# main.net
KiCad netlist of a schematic drawn in Altium Designer
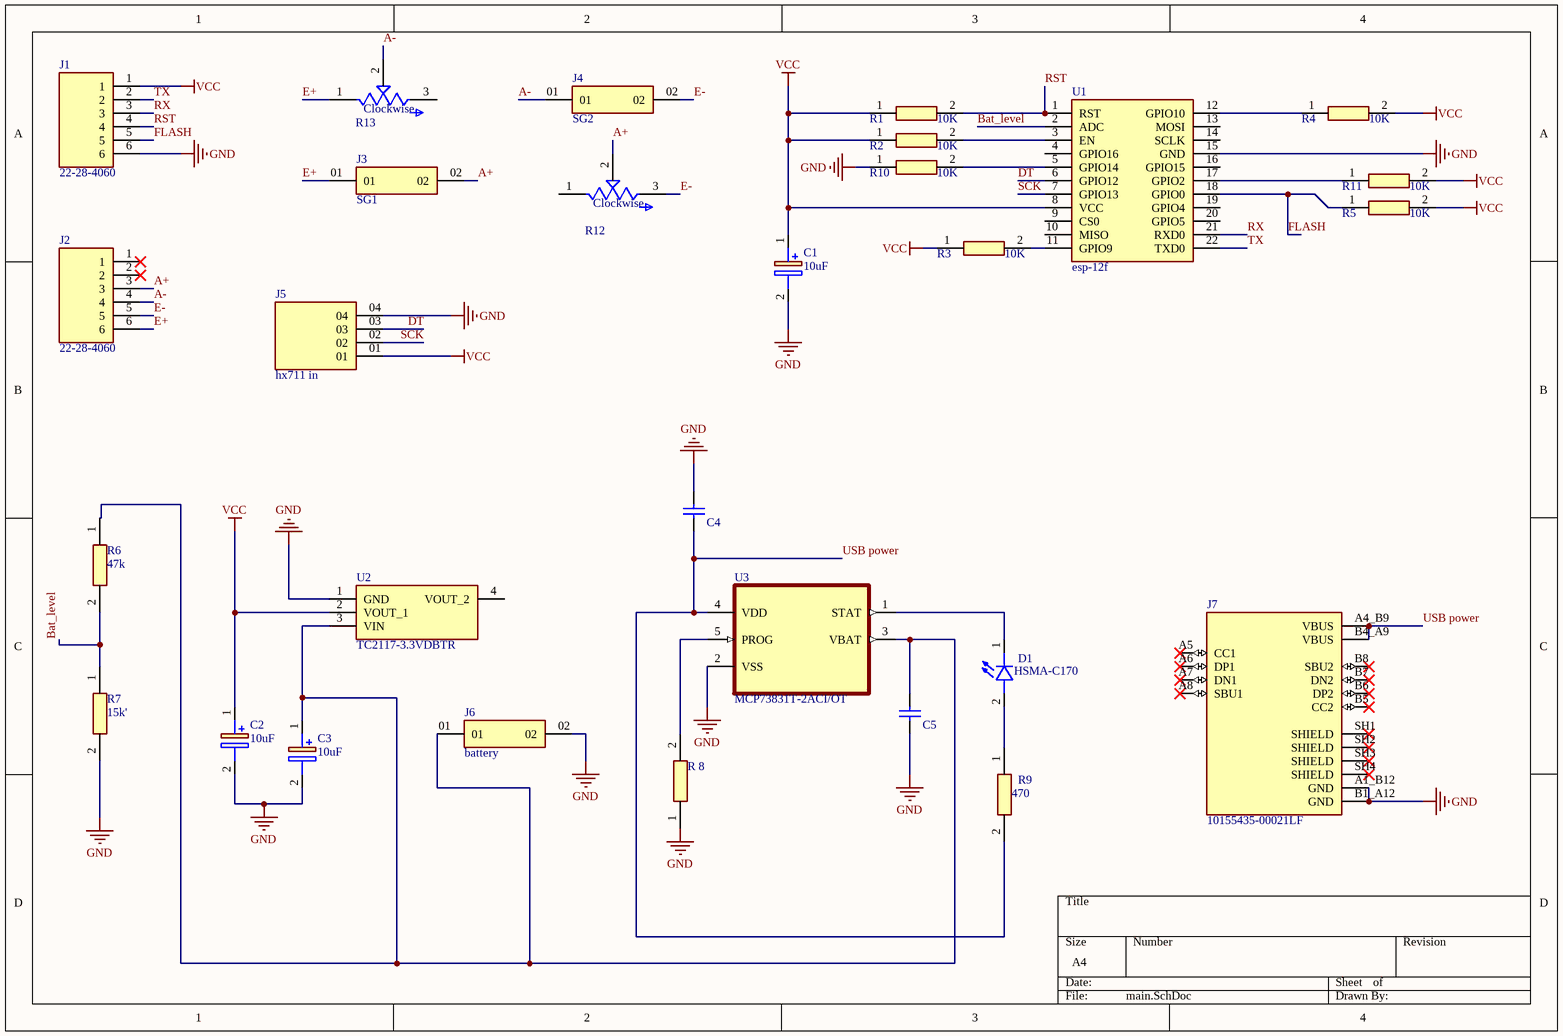
[diagram p0: main.SchDoc]

(export (version "E")
  (design (tool "Eeschema 10.0.6"))
  (components
    (comp (ref "C1")
      (value "10uF")
      (footprint "SamacSys:EEE1AA220WR")
      (description "Capacitor Polarised")
      (fields
        (field (name "MANUFACTURER_PART_NUMBER") "EEE-FN1C100R")
        (field (name "MOUSER PART NUMBER") "667-EEE-FN1C100R")
      )
      (libsource (lib "*") (part "EEE-FN1C100R"))
    )
    (comp (ref "C2")
      (value "10uF")
      (footprint "SamacSys:EEE1AA220WR")
      (description "Capacitor Polarised")
      (fields
        (field (name "MANUFACTURER_PART_NUMBER") "EEE-FN1C100R")
        (field (name "MOUSER PART NUMBER") "667-EEE-FN1C100R")
      )
      (libsource (lib "*") (part "EEE-FN1C100R"))
    )
    (comp (ref "C3")
      (value "10uF")
      (footprint "SamacSys:EEE1AA220WR")
      (description "Capacitor Polarised")
      (fields
        (field (name "MANUFACTURER_PART_NUMBER") "EEE-FN1C100R")
        (field (name "MOUSER PART NUMBER") "667-EEE-FN1C100R")
      )
      (libsource (lib "*") (part "EEE-FN1C100R"))
    )
    (comp (ref "C4")
      (value "4.7uF")
      (footprint "WCAP-CSGP_0805_L2W1.25H0.6_Reflow")
      (description "WCAP-CSGP Multilayer Ceramic Chip Capacitor, General Purpose, size 0805, NP0, 4.7pF, 50VDC")
      (fields
        (field (name "MANUFACTURER PART NUMBER") "885012007049")
        (field (name "MANUFACTURER") "Wurth Elektronik")
      )
      (libsource (lib "WCAP-CSGP") (part "885012007049"))
    )
    (comp (ref "C5")
      (value "4.7uF")
      (footprint "WCAP-CSGP_0805_L2W1.25H0.6_Reflow")
      (description "WCAP-CSGP Multilayer Ceramic Chip Capacitor, General Purpose, size 0805, NP0, 4.7pF, 50VDC")
      (fields
        (field (name "MANUFACTURER PART NUMBER") "885012007049")
        (field (name "MANUFACTURER") "Wurth Elektronik")
      )
      (libsource (lib "WCAP-CSGP") (part "885012007049"))
    )
    (comp (ref "D1")
      (value "HSMA-C170")
      (footprint "LED_HSMA-C170")
      (libsource (lib "HSMA-C170") (part "HSMA-C170"))
    )
    (comp (ref "J1")
      (value "22-28-4060")
      (footprint "HDRV6W66P0X254_1X6_1524X249X838P")
      (description "Connector")
      (fields (field (name "MOUSER PART NUMBER") "538-22-28-4060"))
      (libsource (lib "University of Moratuwa, Sri Lanka") (part "22-28-4060"))
    )
    (comp (ref "J2")
      (value "22-28-4060")
      (footprint "HDRV6W66P0X254_1X6_1524X249X838P")
      (description "Connector")
      (fields (field (name "MOUSER PART NUMBER") "538-22-28-4060"))
      (libsource (lib "University of Moratuwa, Sri Lanka") (part "22-28-4060"))
    )
    (comp (ref "J3")
      (value "SG1")
      (footprint "SAMTEC_MTSW-101-08-G-D-250")
      (fields (field (name "MP") "MTSW-101-08-G-D-250"))
      (libsource (lib "MTSW-101-08-G-D-250") (part "MTSW-101-08-G-D-250"))
    )
    (comp (ref "J4")
      (value "SG2")
      (footprint "SAMTEC_MTSW-101-08-G-D-250")
      (fields (field (name "MP") "MTSW-101-08-G-D-250"))
      (libsource (lib "MTSW-101-08-G-D-250") (part "MTSW-101-08-G-D-250"))
    )
    (comp (ref "J5")
      (value "hx711 in")
      (footprint "SAMTEC_TSW-104-16-G-S")
      (fields (field (name "MP") "TSW-104-16-G-S"))
      (libsource (lib "TSW-104-16-G-S") (part "TSW-104-16-G-S"))
    )
    (comp (ref "J6")
      (value "battery")
      (footprint "SAMTEC_MTSW-101-08-G-D-250")
      (fields (field (name "MP") "MTSW-101-08-G-D-250"))
      (libsource (lib "MTSW-101-08-G-D-250") (part "MTSW-101-08-G-D-250"))
    )
    (comp (ref "J7")
      (value "10155435-00021LF")
      (footprint "AMPHENOL_10155435-00021LF")
      (libsource (lib "10155435-00021LF") (part "10155435-00021LF"))
    )
    (comp (ref "R 8")
      (value "CR0805-JW-202ELF")
      (footprint "SamacSys:RESC2012X60N")
      (description "Resistor")
      (fields (field (name "MOUSER PART NUMBER") "652-CR0805JW-202ELF"))
      (libsource (lib "*") (part "CR0805-JW-202ELF"))
    )
    (comp (ref "R1")
      (value "10K")
      (footprint "SamacSys:RESC2012X60N")
      (description "Resistor")
      (fields
        (field (name "MANUFACTURER_PART_NUMBER") "CHP0805-FX-1002ELF")
        (field (name "MOUSER PART NUMBER") "652-CHP0805FX1002ELF")
      )
      (libsource (lib "") (part "CHP0805-FX-1002ELF_1"))
    )
    (comp (ref "R2")
      (value "10K")
      (footprint "SamacSys:RESC2012X60N")
      (description "Resistor")
      (fields
        (field (name "MANUFACTURER_PART_NUMBER") "CHP0805-FX-1002ELF")
        (field (name "MOUSER PART NUMBER") "652-CHP0805FX1002ELF")
      )
      (libsource (lib "") (part "CHP0805-FX-1002ELF_1"))
    )
    (comp (ref "R3")
      (value "10K")
      (footprint "SamacSys:RESC2012X60N")
      (description "Resistor")
      (fields
        (field (name "MANUFACTURER_PART_NUMBER") "CHP0805-FX-1002ELF")
        (field (name "MOUSER PART NUMBER") "652-CHP0805FX1002ELF")
      )
      (libsource (lib "") (part "CHP0805-FX-1002ELF_1"))
    )
    (comp (ref "R4")
      (value "10K")
      (footprint "SamacSys:RESC2012X60N")
      (description "Resistor")
      (fields
        (field (name "MANUFACTURER_PART_NUMBER") "CHP0805-FX-1002ELF")
        (field (name "MOUSER PART NUMBER") "652-CHP0805FX1002ELF")
      )
      (libsource (lib "") (part "CHP0805-FX-1002ELF_1"))
    )
    (comp (ref "R5")
      (value "10K")
      (footprint "SamacSys:RESC2012X60N")
      (description "Resistor")
      (fields
        (field (name "MANUFACTURER_PART_NUMBER") "CHP0805-FX-1002ELF")
        (field (name "MOUSER PART NUMBER") "652-CHP0805FX1002ELF")
      )
      (libsource (lib "") (part "CHP0805-FX-1002ELF_1"))
    )
    (comp (ref "R6")
      (value "47k")
      (footprint "SamacSys:RESC2012X60N")
      (description "Resistor")
      (fields
        (field (name "MANUFACTURER_PART_NUMBER") "CHP0805-FX-1002ELF")
        (field (name "MOUSER PART NUMBER") "652-CHP0805FX1002ELF")
      )
      (libsource (lib "*") (part "CHP0805-FX-1002ELF"))
    )
    (comp (ref "R7")
      (value "15k'")
      (footprint "SamacSys:RESC2012X60N")
      (description "Resistor")
      (fields
        (field (name "MANUFACTURER_PART_NUMBER") "CHP0805-FX-1002ELF")
        (field (name "MOUSER PART NUMBER") "652-CHP0805FX1002ELF")
      )
      (libsource (lib "*") (part "CHP0805-FX-1002ELF"))
    )
    (comp (ref "R9")
      (value "470")
      (footprint "SamacSys:RESC2012X60N")
      (description "Resistor")
      (fields
        (field (name "MANUFACTURER_PART_NUMBER") "CHP0805-FX-1002ELF")
        (field (name "MOUSER PART NUMBER") "652-CHP0805FX1002ELF")
      )
      (libsource (lib "*") (part "CHP0805-FX-1002ELF"))
    )
    (comp (ref "R10")
      (value "10K")
      (footprint "SamacSys:RESC2012X60N")
      (description "Resistor")
      (fields
        (field (name "MANUFACTURER_PART_NUMBER") "CHP0805-FX-1002ELF")
        (field (name "MOUSER PART NUMBER") "652-CHP0805FX1002ELF")
      )
      (libsource (lib "") (part "CHP0805-FX-1002ELF_1"))
    )
    (comp (ref "R11")
      (value "10K")
      (footprint "SamacSys:RESC2012X60N")
      (description "Resistor")
      (fields
        (field (name "MANUFACTURER_PART_NUMBER") "CHP0805-FX-1002ELF")
        (field (name "MOUSER PART NUMBER") "652-CHP0805FX1002ELF")
      )
      (libsource (lib "") (part "CHP0805-FX-1002ELF_1"))
    )
    (comp (ref "R12")
      (value "PV37W501C01B00")
      (footprint "TRIM_PV37W501C01B00")
      (description "500 Ohms 0.25W, 1/4W PC Pins Through Hole Trimmer Potentiometer Cermet 12.0 Turn Top Adjustment")
      (fields (field (name "MF") "Bourns"))
      (libsource (lib "PV37W501C01B00") (part "PV37W501C01B00"))
    )
    (comp (ref "R13")
      (value "PV37W501C01B00")
      (footprint "TRIM_PV37W501C01B00")
      (description "500 Ohms 0.25W, 1/4W PC Pins Through Hole Trimmer Potentiometer Cermet 12.0 Turn Top Adjustment")
      (fields (field (name "MF") "Bourns"))
      (libsource (lib "PV37W501C01B00") (part "PV37W501C01B00"))
    )
    (comp (ref "U1")
      (value "esp-12f")
      (footprint "SamacSys:esp12f")
      (description "Integrated Circuit")
      (libsource (lib "*") (part "esp-12f"))
    )
    (comp (ref "U2")
      (value "TC2117-3.3VDBTR")
      (footprint "SOT230P700X180-4N")
      (description "Power Supply")
      (fields (field (name "MOUSER PART NUMBER") "579-TC2117-3.3VDBTR"))
      (libsource (lib "*") (part "TC2117-3.3VDBTR"))
    )
    (comp (ref "U3")
      (value "MCP73831T-2ACI/OT")
      (footprint "SOT95P280X145-5N")
      (description "Charger IC Lithium Ion/Polymer SOT-23-5")
      (fields (field (name "MF") "Microchip"))
      (libsource (lib "MCP73831T-2ACI_OT") (part "MCP73831T-2ACI/OT"))
    )
  )
  (nets
    (net (code "1") (name "/A+") (class "Default")
      (node (ref "J2") (pin "3") (pinfunction "3_3") (pintype "passive"))
      (node (ref "J3") (pin "02") (pinfunction "02_02") (pintype "passive"))
      (node (ref "R12") (pin "2") (pinfunction "2_2") (pintype "passive"))
    )
    (net (code "2") (name "/A-") (class "Default")
      (node (ref "J2") (pin "4") (pinfunction "4_4") (pintype "passive"))
      (node (ref "J4") (pin "01") (pinfunction "01_01") (pintype "passive"))
      (node (ref "R13") (pin "2") (pinfunction "2_2") (pintype "passive"))
    )
    (net (code "3") (name "/Bat_level") (class "Default")
      (node (ref "R6") (pin "2") (pinfunction "2_2") (pintype "passive"))
      (node (ref "R7") (pin "1") (pinfunction "1_1") (pintype "passive"))
      (node (ref "U1") (pin "2") (pinfunction "ADC_2") (pintype "passive"))
    )
    (net (code "4") (name "/DT") (class "Default")
      (node (ref "J5") (pin "03") (pinfunction "03_03") (pintype "passive"))
      (node (ref "U1") (pin "6") (pinfunction "GPIO12_6") (pintype "passive"))
    )
    (net (code "5") (name "/E+") (class "Default")
      (node (ref "J2") (pin "6") (pinfunction "6_6") (pintype "passive"))
      (node (ref "J3") (pin "01") (pinfunction "01_01") (pintype "passive"))
      (node (ref "R13") (pin "1") (pinfunction "1_1") (pintype "passive"))
    )
    (net (code "6") (name "/E-") (class "Default")
      (node (ref "J2") (pin "5") (pinfunction "5_5") (pintype "passive"))
      (node (ref "J4") (pin "02") (pinfunction "02_02") (pintype "passive"))
      (node (ref "R12") (pin "3") (pinfunction "3_3") (pintype "passive"))
    )
    (net (code "7") (name "/FLASH") (class "Default")
      (node (ref "J1") (pin "5") (pinfunction "5_5") (pintype "passive"))
      (node (ref "R5") (pin "1") (pinfunction "1_1") (pintype "passive"))
      (node (ref "U1") (pin "18") (pinfunction "GPIO0_18") (pintype "passive"))
    )
    (net (code "8") (name "/RST") (class "Default")
      (node (ref "J1") (pin "4") (pinfunction "4_4") (pintype "passive"))
      (node (ref "R1") (pin "2") (pinfunction "2_2") (pintype "passive"))
      (node (ref "U1") (pin "1") (pinfunction "RST_1") (pintype "passive"))
    )
    (net (code "9") (name "/RX") (class "Default")
      (node (ref "J1") (pin "3") (pinfunction "3_3") (pintype "passive"))
      (node (ref "U1") (pin "21") (pinfunction "RXD0_21") (pintype "passive"))
    )
    (net (code "10") (name "/SCK") (class "Default")
      (node (ref "J5") (pin "02") (pinfunction "02_02") (pintype "passive"))
      (node (ref "U1") (pin "7") (pinfunction "GPIO13_7") (pintype "passive"))
    )
    (net (code "11") (name "/TX") (class "Default")
      (node (ref "J1") (pin "2") (pinfunction "2_2") (pintype "passive"))
      (node (ref "U1") (pin "22") (pinfunction "TXD0_22") (pintype "passive"))
    )
    (net (code "12") (name "/USB power") (class "Default")
      (node (ref "C4") (pin "2") (pinfunction "2_2") (pintype "passive"))
      (node (ref "J7") (pin "A4_B9") (pinfunction "VBUS_A4_B9") (pintype "power_in"))
      (node (ref "J7") (pin "B4_A9") (pinfunction "VBUS_B4_A9") (pintype "power_in"))
      (node (ref "R9") (pin "2") (pinfunction "2_2") (pintype "passive"))
      (node (ref "U3") (pin "4") (pinfunction "VDD_4") (pintype "power_in"))
    )
    (net (code "13") (name "GND") (class "Default")
      (node (ref "C1") (pin "2") (pinfunction "-_2") (pintype "passive"))
      (node (ref "C2") (pin "2") (pinfunction "-_2") (pintype "passive"))
      (node (ref "C3") (pin "2") (pinfunction "-_2") (pintype "passive"))
      (node (ref "C4") (pin "1") (pinfunction "1_1") (pintype "passive"))
      (node (ref "C5") (pin "1") (pinfunction "1_1") (pintype "passive"))
      (node (ref "J1") (pin "6") (pinfunction "6_6") (pintype "passive"))
      (node (ref "J5") (pin "04") (pinfunction "04_04") (pintype "passive"))
      (node (ref "J6") (pin "02") (pinfunction "02_02") (pintype "passive"))
      (node (ref "J7") (pin "A1_B12") (pinfunction "GND_A1_B12") (pintype "power_in"))
      (node (ref "J7") (pin "B1_A12") (pinfunction "GND_B1_A12") (pintype "power_in"))
      (node (ref "R 8") (pin "1") (pinfunction "1_1") (pintype "passive"))
      (node (ref "R10") (pin "1") (pinfunction "1_1") (pintype "passive"))
      (node (ref "R7") (pin "2") (pinfunction "2_2") (pintype "passive"))
      (node (ref "U1") (pin "15") (pinfunction "GND_15") (pintype "passive"))
      (node (ref "U2") (pin "1") (pinfunction "GND_1") (pintype "passive"))
      (node (ref "U3") (pin "2") (pinfunction "VSS_2") (pintype "power_in"))
    )
    (net (code "14") (name "Net-(C3-+)") (class "Default")
      (node (ref "C3") (pin "1") (pinfunction "+_1") (pintype "passive"))
      (node (ref "C5") (pin "2") (pinfunction "2_2") (pintype "passive"))
      (node (ref "J6") (pin "01") (pinfunction "01_01") (pintype "passive"))
      (node (ref "R6") (pin "1") (pinfunction "1_1") (pintype "passive"))
      (node (ref "U2") (pin "3") (pinfunction "VIN_3") (pintype "passive"))
      (node (ref "U3") (pin "3") (pinfunction "VBAT_3") (pintype "output"))
    )
    (net (code "15") (name "Net-(D1-A)") (class "Default")
      (node (ref "D1") (pin "2") (pinfunction "A_2") (pintype "passive"))
      (node (ref "R9") (pin "1") (pinfunction "1_1") (pintype "passive"))
    )
    (net (code "16") (name "Net-(D1-C)") (class "Default")
      (node (ref "D1") (pin "1") (pinfunction "C_1") (pintype "passive"))
      (node (ref "U3") (pin "1") (pinfunction "STAT_1") (pintype "output"))
    )
    (net (code "17") (name "Net-(U1-EN)") (class "Default")
      (node (ref "R2") (pin "2") (pinfunction "2_2") (pintype "passive"))
      (node (ref "U1") (pin "3") (pinfunction "EN_3") (pintype "passive"))
    )
    (net (code "18") (name "Net-(U1-GPIO2)") (class "Default")
      (node (ref "R11") (pin "1") (pinfunction "1_1") (pintype "passive"))
      (node (ref "U1") (pin "17") (pinfunction "GPIO2_17") (pintype "passive"))
    )
    (net (code "19") (name "Net-(U1-GPIO9)") (class "Default")
      (node (ref "R3") (pin "2") (pinfunction "2_2") (pintype "passive"))
      (node (ref "U1") (pin "11") (pinfunction "GPIO9_11") (pintype "passive"))
    )
    (net (code "20") (name "Net-(U1-GPIO10)") (class "Default")
      (node (ref "R4") (pin "1") (pinfunction "1_1") (pintype "passive"))
      (node (ref "U1") (pin "12") (pinfunction "GPIO10_12") (pintype "passive"))
    )
    (net (code "21") (name "Net-(U1-GPIO14)") (class "Default")
      (node (ref "R10") (pin "2") (pinfunction "2_2") (pintype "passive"))
      (node (ref "U1") (pin "5") (pinfunction "GPIO14_5") (pintype "passive"))
    )
    (net (code "22") (name "Net-(U3-PROG)") (class "Default")
      (node (ref "R 8") (pin "2") (pinfunction "2_2") (pintype "passive"))
      (node (ref "U3") (pin "5") (pinfunction "PROG_5") (pintype "input"))
    )
    (net (code "23") (name "VCC") (class "Default")
      (node (ref "C1") (pin "1") (pinfunction "+_1") (pintype "passive"))
      (node (ref "C2") (pin "1") (pinfunction "+_1") (pintype "passive"))
      (node (ref "J1") (pin "1") (pinfunction "1_1") (pintype "passive"))
      (node (ref "J5") (pin "01") (pinfunction "01_01") (pintype "passive"))
      (node (ref "R1") (pin "1") (pinfunction "1_1") (pintype "passive"))
      (node (ref "R11") (pin "2") (pinfunction "2_2") (pintype "passive"))
      (node (ref "R2") (pin "1") (pinfunction "1_1") (pintype "passive"))
      (node (ref "R3") (pin "1") (pinfunction "1_1") (pintype "passive"))
      (node (ref "R4") (pin "2") (pinfunction "2_2") (pintype "passive"))
      (node (ref "R5") (pin "2") (pinfunction "2_2") (pintype "passive"))
      (node (ref "U1") (pin "8") (pinfunction "VCC_8") (pintype "passive"))
      (node (ref "U2") (pin "2") (pinfunction "VOUT_1_2") (pintype "passive"))
    )
    (net (code "24") (name "unconnected-(J2-Pad1)") (class "Default")
      (node (ref "J2") (pin "1") (pinfunction "1_1") (pintype "passive+no_connect"))
    )
    (net (code "25") (name "unconnected-(J2-Pad2)") (class "Default")
      (node (ref "J2") (pin "2") (pinfunction "2_2") (pintype "passive+no_connect"))
    )
    (net (code "26") (name "unconnected-(J7-CC1-PadA5)") (class "Default")
      (node (ref "J7") (pin "A5") (pinfunction "CC1_A5") (pintype "bidirectional+no_connect"))
    )
    (net (code "27") (name "unconnected-(J7-CC2-PadB5)") (class "Default")
      (node (ref "J7") (pin "B5") (pinfunction "CC2_B5") (pintype "bidirectional+no_connect"))
    )
    (net (code "28") (name "unconnected-(J7-DN1-PadA7)") (class "Default")
      (node (ref "J7") (pin "A7") (pinfunction "DN1_A7") (pintype "bidirectional+no_connect"))
    )
    (net (code "29") (name "unconnected-(J7-DN2-PadB7)") (class "Default")
      (node (ref "J7") (pin "B7") (pinfunction "DN2_B7") (pintype "bidirectional+no_connect"))
    )
    (net (code "30") (name "unconnected-(J7-DP1-PadA6)") (class "Default")
      (node (ref "J7") (pin "A6") (pinfunction "DP1_A6") (pintype "bidirectional+no_connect"))
    )
    (net (code "31") (name "unconnected-(J7-DP2-PadB6)") (class "Default")
      (node (ref "J7") (pin "B6") (pinfunction "DP2_B6") (pintype "bidirectional+no_connect"))
    )
    (net (code "32") (name "unconnected-(J7-SBU1-PadA8)") (class "Default")
      (node (ref "J7") (pin "A8") (pinfunction "SBU1_A8") (pintype "bidirectional+no_connect"))
    )
    (net (code "33") (name "unconnected-(J7-SBU2-PadB8)") (class "Default")
      (node (ref "J7") (pin "B8") (pinfunction "SBU2_B8") (pintype "bidirectional+no_connect"))
    )
    (net (code "34") (name "unconnected-(J7-SHIELD-PadSH1)") (class "Default")
      (node (ref "J7") (pin "SH1") (pinfunction "SHIELD_SH1") (pintype "passive+no_connect"))
    )
    (net (code "35") (name "unconnected-(J7-SHIELD-PadSH2)") (class "Default")
      (node (ref "J7") (pin "SH2") (pinfunction "SHIELD_SH2") (pintype "passive+no_connect"))
    )
    (net (code "36") (name "unconnected-(J7-SHIELD-PadSH3)") (class "Default")
      (node (ref "J7") (pin "SH3") (pinfunction "SHIELD_SH3") (pintype "passive+no_connect"))
    )
    (net (code "37") (name "unconnected-(J7-SHIELD-PadSH4)") (class "Default")
      (node (ref "J7") (pin "SH4") (pinfunction "SHIELD_SH4") (pintype "passive+no_connect"))
    )
    (net (code "38") (name "unconnected-(R12-Pad1)") (class "Default")
      (node (ref "R12") (pin "1") (pinfunction "1_1") (pintype "passive"))
    )
    (net (code "39") (name "unconnected-(R13-Pad3)") (class "Default")
      (node (ref "R13") (pin "3") (pinfunction "3_3") (pintype "passive"))
    )
    (net (code "40") (name "unconnected-(U1-CS0-Pad9)") (class "Default")
      (node (ref "U1") (pin "9") (pinfunction "CS0_9") (pintype "passive"))
    )
    (net (code "41") (name "unconnected-(U1-GPIO4-Pad19)") (class "Default")
      (node (ref "U1") (pin "19") (pinfunction "GPIO4_19") (pintype "passive"))
    )
    (net (code "42") (name "unconnected-(U1-GPIO5-Pad20)") (class "Default")
      (node (ref "U1") (pin "20") (pinfunction "GPIO5_20") (pintype "passive"))
    )
    (net (code "43") (name "unconnected-(U1-GPIO15-Pad16)") (class "Default")
      (node (ref "U1") (pin "16") (pinfunction "GPIO15_16") (pintype "passive"))
    )
    (net (code "44") (name "unconnected-(U1-GPIO16-Pad4)") (class "Default")
      (node (ref "U1") (pin "4") (pinfunction "GPIO16_4") (pintype "passive"))
    )
    (net (code "45") (name "unconnected-(U1-MISO-Pad10)") (class "Default")
      (node (ref "U1") (pin "10") (pinfunction "MISO_10") (pintype "passive"))
    )
    (net (code "46") (name "unconnected-(U1-MOSI-Pad13)") (class "Default")
      (node (ref "U1") (pin "13") (pinfunction "MOSI_13") (pintype "passive"))
    )
    (net (code "47") (name "unconnected-(U1-SCLK-Pad14)") (class "Default")
      (node (ref "U1") (pin "14") (pinfunction "SCLK_14") (pintype "passive"))
    )
    (net (code "48") (name "unconnected-(U2-VOUT_2-Pad4)") (class "Default")
      (node (ref "U2") (pin "4") (pinfunction "VOUT_2_4") (pintype "passive"))
    )
  )
)
